# TinyCube12b_Lib.net
KiCad netlist of a schematic drawn in EAGLE
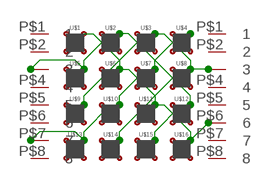
[diagram p0: schematic, sheet 1]

(export (version "E")
  (design (tool "Eeschema 10.0.6"))
  (components
    (comp (ref "U$1")
      (value "PILLAR")
      (footprint "eagle-import:10MIL")
      (libsource (lib "eagle-import") (part "PILLAR"))
    )
    (comp (ref "U$2")
      (value "PILLAR")
      (footprint "eagle-import:10MIL")
      (libsource (lib "eagle-import") (part "PILLAR"))
    )
    (comp (ref "U$3")
      (value "PILLAR")
      (footprint "eagle-import:10MIL")
      (libsource (lib "eagle-import") (part "PILLAR"))
    )
    (comp (ref "U$4")
      (value "PILLAR")
      (footprint "eagle-import:10MIL")
      (libsource (lib "eagle-import") (part "PILLAR"))
    )
    (comp (ref "U$5")
      (value "PILLAR")
      (footprint "eagle-import:10MIL")
      (libsource (lib "eagle-import") (part "PILLAR"))
    )
    (comp (ref "U$6")
      (value "PILLAR")
      (footprint "eagle-import:10MIL")
      (libsource (lib "eagle-import") (part "PILLAR"))
    )
    (comp (ref "U$7")
      (value "PILLAR")
      (footprint "eagle-import:10MIL")
      (libsource (lib "eagle-import") (part "PILLAR"))
    )
    (comp (ref "U$8")
      (value "PILLAR")
      (footprint "eagle-import:10MIL")
      (libsource (lib "eagle-import") (part "PILLAR"))
    )
    (comp (ref "U$9")
      (value "PILLAR")
      (footprint "eagle-import:10MIL")
      (libsource (lib "eagle-import") (part "PILLAR"))
    )
    (comp (ref "U$10")
      (value "PILLAR")
      (footprint "eagle-import:10MIL")
      (libsource (lib "eagle-import") (part "PILLAR"))
    )
    (comp (ref "U$11")
      (value "PILLAR")
      (footprint "eagle-import:10MIL")
      (libsource (lib "eagle-import") (part "PILLAR"))
    )
    (comp (ref "U$12")
      (value "PILLAR")
      (footprint "eagle-import:10MIL")
      (libsource (lib "eagle-import") (part "PILLAR"))
    )
    (comp (ref "U$13")
      (value "PILLAR")
      (footprint "eagle-import:10MIL")
      (libsource (lib "eagle-import") (part "PILLAR"))
    )
    (comp (ref "U$14")
      (value "PILLAR")
      (footprint "eagle-import:10MIL")
      (libsource (lib "eagle-import") (part "PILLAR"))
    )
    (comp (ref "U$15")
      (value "PILLAR")
      (footprint "eagle-import:10MIL")
      (libsource (lib "eagle-import") (part "PILLAR"))
    )
    (comp (ref "U$16")
      (value "PILLAR")
      (footprint "eagle-import:10MIL")
      (libsource (lib "eagle-import") (part "PILLAR"))
    )
    (comp (ref "U$17")
      (value "TINY_HEADER_DEV")
      (footprint "eagle-import:TINY_HEADER_PKG")
      (libsource (lib "eagle-import") (part "TINY_HEADER_DEV"))
    )
    (comp (ref "U$18")
      (value "TINY_HEADER_DEV")
      (footprint "eagle-import:TINY_HEADER_PKG")
      (libsource (lib "eagle-import") (part "TINY_HEADER_DEV"))
    )
  )
  (nets
    (net (code "1") (name "Net-(U$1-G)") (class "Default")
      (node (ref "U$1") (pin "+") (pinfunction "G_+") (pintype "bidirectional"))
      (node (ref "U$11") (pin "+") (pinfunction "G_+") (pintype "bidirectional"))
      (node (ref "U$16") (pin "+") (pinfunction "G_+") (pintype "bidirectional"))
      (node (ref "U$18") (pin "P$6") (pinfunction "6_P$6") (pintype "bidirectional"))
      (node (ref "U$6") (pin "+") (pinfunction "G_+") (pintype "bidirectional"))
    )
    (net (code "2") (name "Net-(U$10-G)") (class "Default")
      (node (ref "U$10") (pin "+") (pinfunction "G_+") (pintype "bidirectional"))
      (node (ref "U$13") (pin "+") (pinfunction "G_+") (pintype "bidirectional"))
      (node (ref "U$17") (pin "P$7") (pinfunction "7_P$7") (pintype "bidirectional"))
      (node (ref "U$4") (pin "+") (pinfunction "G_+") (pintype "bidirectional"))
      (node (ref "U$7") (pin "+") (pinfunction "G_+") (pintype "bidirectional"))
    )
    (net (code "3") (name "Net-(U$12-G)") (class "Default")
      (node (ref "U$12") (pin "+") (pinfunction "G_+") (pintype "bidirectional"))
      (node (ref "U$15") (pin "+") (pinfunction "G_+") (pintype "bidirectional"))
      (node (ref "U$17") (pin "P$3") (pinfunction "3_P$3") (pintype "bidirectional"))
      (node (ref "U$2") (pin "+") (pinfunction "G_+") (pintype "bidirectional"))
      (node (ref "U$5") (pin "+") (pinfunction "G_+") (pintype "bidirectional"))
    )
    (net (code "4") (name "Net-(U$14-G)") (class "Default")
      (node (ref "U$14") (pin "+") (pinfunction "G_+") (pintype "bidirectional"))
      (node (ref "U$18") (pin "P$3") (pinfunction "3_P$3") (pintype "bidirectional"))
      (node (ref "U$3") (pin "+") (pinfunction "G_+") (pintype "bidirectional"))
      (node (ref "U$8") (pin "+") (pinfunction "G_+") (pintype "bidirectional"))
      (node (ref "U$9") (pin "+") (pinfunction "G_+") (pintype "bidirectional"))
    )
    (net (code "5") (name "unconnected-(U$1-A-PadG)") (class "Default")
      (node (ref "U$1") (pin "G") (pinfunction "A_G") (pintype "bidirectional"))
    )
    (net (code "6") (name "unconnected-(U$1-B-PadR)") (class "Default")
      (node (ref "U$1") (pin "R") (pinfunction "B_R") (pintype "bidirectional"))
    )
    (net (code "7") (name "unconnected-(U$1-R-PadB)") (class "Default")
      (node (ref "U$1") (pin "B") (pinfunction "R_B") (pintype "bidirectional"))
    )
    (net (code "8") (name "unconnected-(U$2-A-PadG)") (class "Default")
      (node (ref "U$2") (pin "G") (pinfunction "A_G") (pintype "bidirectional"))
    )
    (net (code "9") (name "unconnected-(U$2-B-PadR)") (class "Default")
      (node (ref "U$2") (pin "R") (pinfunction "B_R") (pintype "bidirectional"))
    )
    (net (code "10") (name "unconnected-(U$2-R-PadB)") (class "Default")
      (node (ref "U$2") (pin "B") (pinfunction "R_B") (pintype "bidirectional"))
    )
    (net (code "11") (name "unconnected-(U$3-A-PadG)") (class "Default")
      (node (ref "U$3") (pin "G") (pinfunction "A_G") (pintype "bidirectional"))
    )
    (net (code "12") (name "unconnected-(U$3-B-PadR)") (class "Default")
      (node (ref "U$3") (pin "R") (pinfunction "B_R") (pintype "bidirectional"))
    )
    (net (code "13") (name "unconnected-(U$3-R-PadB)") (class "Default")
      (node (ref "U$3") (pin "B") (pinfunction "R_B") (pintype "bidirectional"))
    )
    (net (code "14") (name "unconnected-(U$4-A-PadG)") (class "Default")
      (node (ref "U$4") (pin "G") (pinfunction "A_G") (pintype "bidirectional"))
    )
    (net (code "15") (name "unconnected-(U$4-B-PadR)") (class "Default")
      (node (ref "U$4") (pin "R") (pinfunction "B_R") (pintype "bidirectional"))
    )
    (net (code "16") (name "unconnected-(U$4-R-PadB)") (class "Default")
      (node (ref "U$4") (pin "B") (pinfunction "R_B") (pintype "bidirectional"))
    )
    (net (code "17") (name "unconnected-(U$5-A-PadG)") (class "Default")
      (node (ref "U$5") (pin "G") (pinfunction "A_G") (pintype "bidirectional"))
    )
    (net (code "18") (name "unconnected-(U$5-B-PadR)") (class "Default")
      (node (ref "U$5") (pin "R") (pinfunction "B_R") (pintype "bidirectional"))
    )
    (net (code "19") (name "unconnected-(U$5-R-PadB)") (class "Default")
      (node (ref "U$5") (pin "B") (pinfunction "R_B") (pintype "bidirectional"))
    )
    (net (code "20") (name "unconnected-(U$6-A-PadG)") (class "Default")
      (node (ref "U$6") (pin "G") (pinfunction "A_G") (pintype "bidirectional"))
    )
    (net (code "21") (name "unconnected-(U$6-B-PadR)") (class "Default")
      (node (ref "U$6") (pin "R") (pinfunction "B_R") (pintype "bidirectional"))
    )
    (net (code "22") (name "unconnected-(U$6-R-PadB)") (class "Default")
      (node (ref "U$6") (pin "B") (pinfunction "R_B") (pintype "bidirectional"))
    )
    (net (code "23") (name "unconnected-(U$7-A-PadG)") (class "Default")
      (node (ref "U$7") (pin "G") (pinfunction "A_G") (pintype "bidirectional"))
    )
    (net (code "24") (name "unconnected-(U$7-B-PadR)") (class "Default")
      (node (ref "U$7") (pin "R") (pinfunction "B_R") (pintype "bidirectional"))
    )
    (net (code "25") (name "unconnected-(U$7-R-PadB)") (class "Default")
      (node (ref "U$7") (pin "B") (pinfunction "R_B") (pintype "bidirectional"))
    )
    (net (code "26") (name "unconnected-(U$8-A-PadG)") (class "Default")
      (node (ref "U$8") (pin "G") (pinfunction "A_G") (pintype "bidirectional"))
    )
    (net (code "27") (name "unconnected-(U$8-B-PadR)") (class "Default")
      (node (ref "U$8") (pin "R") (pinfunction "B_R") (pintype "bidirectional"))
    )
    (net (code "28") (name "unconnected-(U$8-R-PadB)") (class "Default")
      (node (ref "U$8") (pin "B") (pinfunction "R_B") (pintype "bidirectional"))
    )
    (net (code "29") (name "unconnected-(U$9-A-PadG)") (class "Default")
      (node (ref "U$9") (pin "G") (pinfunction "A_G") (pintype "bidirectional"))
    )
    (net (code "30") (name "unconnected-(U$9-B-PadR)") (class "Default")
      (node (ref "U$9") (pin "R") (pinfunction "B_R") (pintype "bidirectional"))
    )
    (net (code "31") (name "unconnected-(U$9-R-PadB)") (class "Default")
      (node (ref "U$9") (pin "B") (pinfunction "R_B") (pintype "bidirectional"))
    )
    (net (code "32") (name "unconnected-(U$10-A-PadG)") (class "Default")
      (node (ref "U$10") (pin "G") (pinfunction "A_G") (pintype "bidirectional"))
    )
    (net (code "33") (name "unconnected-(U$10-B-PadR)") (class "Default")
      (node (ref "U$10") (pin "R") (pinfunction "B_R") (pintype "bidirectional"))
    )
    (net (code "34") (name "unconnected-(U$10-R-PadB)") (class "Default")
      (node (ref "U$10") (pin "B") (pinfunction "R_B") (pintype "bidirectional"))
    )
    (net (code "35") (name "unconnected-(U$11-A-PadG)") (class "Default")
      (node (ref "U$11") (pin "G") (pinfunction "A_G") (pintype "bidirectional"))
    )
    (net (code "36") (name "unconnected-(U$11-B-PadR)") (class "Default")
      (node (ref "U$11") (pin "R") (pinfunction "B_R") (pintype "bidirectional"))
    )
    (net (code "37") (name "unconnected-(U$11-R-PadB)") (class "Default")
      (node (ref "U$11") (pin "B") (pinfunction "R_B") (pintype "bidirectional"))
    )
    (net (code "38") (name "unconnected-(U$12-A-PadG)") (class "Default")
      (node (ref "U$12") (pin "G") (pinfunction "A_G") (pintype "bidirectional"))
    )
    (net (code "39") (name "unconnected-(U$12-B-PadR)") (class "Default")
      (node (ref "U$12") (pin "R") (pinfunction "B_R") (pintype "bidirectional"))
    )
    (net (code "40") (name "unconnected-(U$12-R-PadB)") (class "Default")
      (node (ref "U$12") (pin "B") (pinfunction "R_B") (pintype "bidirectional"))
    )
    (net (code "41") (name "unconnected-(U$13-A-PadG)") (class "Default")
      (node (ref "U$13") (pin "G") (pinfunction "A_G") (pintype "bidirectional"))
    )
    (net (code "42") (name "unconnected-(U$13-B-PadR)") (class "Default")
      (node (ref "U$13") (pin "R") (pinfunction "B_R") (pintype "bidirectional"))
    )
    (net (code "43") (name "unconnected-(U$13-R-PadB)") (class "Default")
      (node (ref "U$13") (pin "B") (pinfunction "R_B") (pintype "bidirectional"))
    )
    (net (code "44") (name "unconnected-(U$14-A-PadG)") (class "Default")
      (node (ref "U$14") (pin "G") (pinfunction "A_G") (pintype "bidirectional"))
    )
    (net (code "45") (name "unconnected-(U$14-B-PadR)") (class "Default")
      (node (ref "U$14") (pin "R") (pinfunction "B_R") (pintype "bidirectional"))
    )
    (net (code "46") (name "unconnected-(U$14-R-PadB)") (class "Default")
      (node (ref "U$14") (pin "B") (pinfunction "R_B") (pintype "bidirectional"))
    )
    (net (code "47") (name "unconnected-(U$15-A-PadG)") (class "Default")
      (node (ref "U$15") (pin "G") (pinfunction "A_G") (pintype "bidirectional"))
    )
    (net (code "48") (name "unconnected-(U$15-B-PadR)") (class "Default")
      (node (ref "U$15") (pin "R") (pinfunction "B_R") (pintype "bidirectional"))
    )
    (net (code "49") (name "unconnected-(U$15-R-PadB)") (class "Default")
      (node (ref "U$15") (pin "B") (pinfunction "R_B") (pintype "bidirectional"))
    )
    (net (code "50") (name "unconnected-(U$16-A-PadG)") (class "Default")
      (node (ref "U$16") (pin "G") (pinfunction "A_G") (pintype "bidirectional"))
    )
    (net (code "51") (name "unconnected-(U$16-B-PadR)") (class "Default")
      (node (ref "U$16") (pin "R") (pinfunction "B_R") (pintype "bidirectional"))
    )
    (net (code "52") (name "unconnected-(U$16-R-PadB)") (class "Default")
      (node (ref "U$16") (pin "B") (pinfunction "R_B") (pintype "bidirectional"))
    )
    (net (code "53") (name "unconnected-(U$17-1-PadP$1)") (class "Default")
      (node (ref "U$17") (pin "P$1") (pinfunction "1_P$1") (pintype "input"))
    )
    (net (code "54") (name "unconnected-(U$17-2-PadP$2)") (class "Default")
      (node (ref "U$17") (pin "P$2") (pinfunction "2_P$2") (pintype "bidirectional"))
    )
    (net (code "55") (name "unconnected-(U$17-4-PadP$4)") (class "Default")
      (node (ref "U$17") (pin "P$4") (pinfunction "4_P$4") (pintype "bidirectional"))
    )
    (net (code "56") (name "unconnected-(U$17-5-PadP$5)") (class "Default")
      (node (ref "U$17") (pin "P$5") (pinfunction "5_P$5") (pintype "bidirectional"))
    )
    (net (code "57") (name "unconnected-(U$17-6-PadP$6)") (class "Default")
      (node (ref "U$17") (pin "P$6") (pinfunction "6_P$6") (pintype "bidirectional"))
    )
    (net (code "58") (name "unconnected-(U$17-8-PadP$8)") (class "Default")
      (node (ref "U$17") (pin "P$8") (pinfunction "8_P$8") (pintype "bidirectional"))
    )
    (net (code "59") (name "unconnected-(U$18-1-PadP$1)") (class "Default")
      (node (ref "U$18") (pin "P$1") (pinfunction "1_P$1") (pintype "input"))
    )
    (net (code "60") (name "unconnected-(U$18-2-PadP$2)") (class "Default")
      (node (ref "U$18") (pin "P$2") (pinfunction "2_P$2") (pintype "bidirectional"))
    )
    (net (code "61") (name "unconnected-(U$18-4-PadP$4)") (class "Default")
      (node (ref "U$18") (pin "P$4") (pinfunction "4_P$4") (pintype "bidirectional"))
    )
    (net (code "62") (name "unconnected-(U$18-5-PadP$5)") (class "Default")
      (node (ref "U$18") (pin "P$5") (pinfunction "5_P$5") (pintype "bidirectional"))
    )
    (net (code "63") (name "unconnected-(U$18-7-PadP$7)") (class "Default")
      (node (ref "U$18") (pin "P$7") (pinfunction "7_P$7") (pintype "bidirectional"))
    )
    (net (code "64") (name "unconnected-(U$18-8-PadP$8)") (class "Default")
      (node (ref "U$18") (pin "P$8") (pinfunction "8_P$8") (pintype "bidirectional"))
    )
  )
)
